# Led.net
KiCad netlist of a schematic drawn in Altium Designer
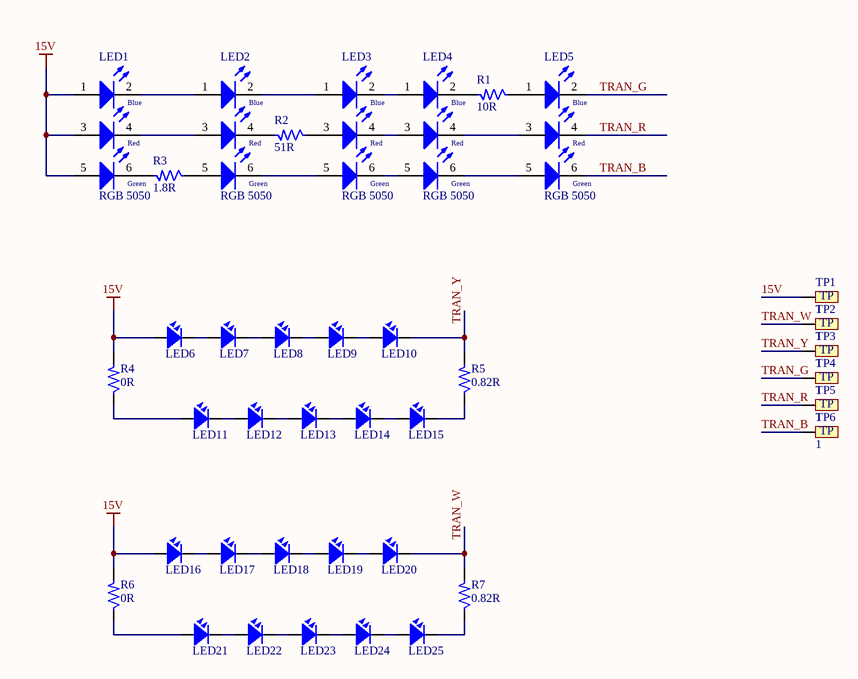
[diagram p0: Led.SchDoc]

(export (version "E")
  (design (tool "Eeschema 10.0.6"))
  (components
    (comp (ref "LED1")
      (value "RGB 5050")
      (footprint "HueNguyenLib:LED RGB 5050")
      (libsource (lib "HueNguyenLib") (part "LED RGB 5050 1.5W"))
    )
    (comp (ref "LED2")
      (value "RGB 5050")
      (footprint "HueNguyenLib:LED RGB 5050")
      (libsource (lib "HueNguyenLib") (part "LED RGB 5050 1.5W"))
    )
    (comp (ref "LED3")
      (value "RGB 5050")
      (footprint "HueNguyenLib:LED RGB 5050")
      (libsource (lib "HueNguyenLib") (part "LED RGB 5050 1.5W"))
    )
    (comp (ref "LED4")
      (value "RGB 5050")
      (footprint "HueNguyenLib:LED RGB 5050")
      (libsource (lib "HueNguyenLib") (part "LED RGB 5050 1.5W"))
    )
    (comp (ref "LED5")
      (value "RGB 5050")
      (footprint "HueNguyenLib:LED RGB 5050")
      (libsource (lib "HueNguyenLib") (part "LED RGB 5050 1.5W"))
    )
    (comp (ref "LED6")
      (value "3030")
      (footprint "HueNguyenLib:LED 3030")
      (libsource (lib "Thu Vien Chuan") (part "LED SMD"))
    )
    (comp (ref "LED7")
      (value "3030")
      (footprint "HueNguyenLib:LED 3030")
      (libsource (lib "Thu Vien Chuan") (part "LED SMD"))
    )
    (comp (ref "LED8")
      (value "3030")
      (footprint "HueNguyenLib:LED 3030")
      (libsource (lib "Thu Vien Chuan") (part "LED SMD"))
    )
    (comp (ref "LED9")
      (value "3030")
      (footprint "HueNguyenLib:LED 3030")
      (libsource (lib "Thu Vien Chuan") (part "LED SMD"))
    )
    (comp (ref "LED10")
      (value "3030")
      (footprint "HueNguyenLib:LED 3030")
      (libsource (lib "Thu Vien Chuan") (part "LED SMD"))
    )
    (comp (ref "LED11")
      (value "3030")
      (footprint "HueNguyenLib:LED 3030")
      (libsource (lib "Thu Vien Chuan") (part "LED SMD"))
    )
    (comp (ref "LED12")
      (value "3030")
      (footprint "HueNguyenLib:LED 3030")
      (libsource (lib "Thu Vien Chuan") (part "LED SMD"))
    )
    (comp (ref "LED13")
      (value "3030")
      (footprint "HueNguyenLib:LED 3030")
      (libsource (lib "Thu Vien Chuan") (part "LED SMD"))
    )
    (comp (ref "LED14")
      (value "3030")
      (footprint "HueNguyenLib:LED 3030")
      (libsource (lib "Thu Vien Chuan") (part "LED SMD"))
    )
    (comp (ref "LED15")
      (value "3030")
      (footprint "HueNguyenLib:LED 3030")
      (libsource (lib "Thu Vien Chuan") (part "LED SMD"))
    )
    (comp (ref "LED16")
      (value "3030")
      (footprint "HueNguyenLib:LED 3030")
      (libsource (lib "Thu Vien Chuan") (part "LED SMD"))
    )
    (comp (ref "LED17")
      (value "3030")
      (footprint "HueNguyenLib:LED 3030")
      (libsource (lib "Thu Vien Chuan") (part "LED SMD"))
    )
    (comp (ref "LED18")
      (value "3030")
      (footprint "HueNguyenLib:LED 3030")
      (libsource (lib "Thu Vien Chuan") (part "LED SMD"))
    )
    (comp (ref "LED19")
      (value "3030")
      (footprint "HueNguyenLib:LED 3030")
      (libsource (lib "Thu Vien Chuan") (part "LED SMD"))
    )
    (comp (ref "LED20")
      (value "3030")
      (footprint "HueNguyenLib:LED 3030")
      (libsource (lib "Thu Vien Chuan") (part "LED SMD"))
    )
    (comp (ref "LED21")
      (value "3030")
      (footprint "HueNguyenLib:LED 3030")
      (libsource (lib "Thu Vien Chuan") (part "LED SMD"))
    )
    (comp (ref "LED22")
      (value "3030")
      (footprint "HueNguyenLib:LED 3030")
      (libsource (lib "Thu Vien Chuan") (part "LED SMD"))
    )
    (comp (ref "LED23")
      (value "3030")
      (footprint "HueNguyenLib:LED 3030")
      (libsource (lib "Thu Vien Chuan") (part "LED SMD"))
    )
    (comp (ref "LED24")
      (value "3030")
      (footprint "HueNguyenLib:LED 3030")
      (libsource (lib "Thu Vien Chuan") (part "LED SMD"))
    )
    (comp (ref "LED25")
      (value "3030")
      (footprint "HueNguyenLib:LED 3030")
      (libsource (lib "Thu Vien Chuan") (part "LED SMD"))
    )
    (comp (ref "R1")
      (value "10R")
      (footprint "SM-RES-1206")
      (description "Resistor 1/4W")
      (libsource (lib "Thu Vien Chuan") (part "R"))
    )
    (comp (ref "R2")
      (value "51R")
      (footprint "SM-RES-1206")
      (description "Resistor 1/4W")
      (libsource (lib "Thu Vien Chuan") (part "R"))
    )
    (comp (ref "R3")
      (value "1.8R")
      (footprint "SM-RES-1206")
      (description "Resistor 1/4W")
      (libsource (lib "Thu Vien Chuan") (part "R"))
    )
    (comp (ref "R4")
      (value "0R")
      (footprint "SM-RES-1206")
      (description "Resistor 1/4W")
      (libsource (lib "Thu Vien Chuan") (part "R"))
    )
    (comp (ref "R5")
      (value "0.82R")
      (footprint "SM-RES-1206")
      (description "Resistor 1/4W")
      (libsource (lib "Thu Vien Chuan") (part "R"))
    )
    (comp (ref "R6")
      (value "0R")
      (footprint "SM-RES-1206")
      (description "Resistor 1/4W")
      (libsource (lib "Thu Vien Chuan") (part "R"))
    )
    (comp (ref "R7")
      (value "0.82R")
      (footprint "SM-RES-1206")
      (description "Resistor 1/4W")
      (libsource (lib "Thu Vien Chuan") (part "R"))
    )
    (comp (ref "TP1")
      (value "1")
      (footprint "TP")
      (description "CONNECT 1")
      (libsource (lib "Thu Vien Chuan") (part "TP"))
    )
    (comp (ref "TP2")
      (value "1")
      (footprint "TP")
      (description "CONNECT 1")
      (libsource (lib "Thu Vien Chuan") (part "TP"))
    )
    (comp (ref "TP3")
      (value "1")
      (footprint "TP")
      (description "CONNECT 1")
      (libsource (lib "Thu Vien Chuan") (part "TP"))
    )
    (comp (ref "TP4")
      (value "1")
      (footprint "TP")
      (description "CONNECT 1")
      (libsource (lib "Thu Vien Chuan") (part "TP"))
    )
    (comp (ref "TP5")
      (value "1")
      (footprint "TP")
      (description "CONNECT 1")
      (libsource (lib "Thu Vien Chuan") (part "TP"))
    )
    (comp (ref "TP6")
      (value "1")
      (footprint "TP")
      (description "CONNECT 1")
      (libsource (lib "Thu Vien Chuan") (part "TP"))
    )
  )
  (nets
    (net (code "1") (name "/TRAN_B") (class "Default")
      (node (ref "LED5") (pin "6") (pintype "passive"))
      (node (ref "TP6") (pin "TP1") (pinfunction "0_TP1") (pintype "passive"))
    )
    (net (code "2") (name "/TRAN_G") (class "Default")
      (node (ref "LED5") (pin "2") (pintype "passive"))
      (node (ref "TP4") (pin "TP1") (pinfunction "0_TP1") (pintype "passive"))
    )
    (net (code "3") (name "/TRAN_R") (class "Default")
      (node (ref "LED5") (pin "4") (pintype "passive"))
      (node (ref "TP5") (pin "TP1") (pinfunction "0_TP1") (pintype "passive"))
    )
    (net (code "4") (name "/TRAN_W") (class "Default")
      (node (ref "LED20") (pin "2") (pinfunction "2_2") (pintype "passive"))
      (node (ref "R7") (pin "2") (pinfunction "2_2") (pintype "passive"))
      (node (ref "TP2") (pin "TP1") (pinfunction "0_TP1") (pintype "passive"))
    )
    (net (code "5") (name "/TRAN_Y") (class "Default")
      (node (ref "LED10") (pin "2") (pinfunction "2_2") (pintype "passive"))
      (node (ref "R5") (pin "2") (pinfunction "2_2") (pintype "passive"))
      (node (ref "TP3") (pin "TP1") (pinfunction "0_TP1") (pintype "passive"))
    )
    (net (code "6") (name "15V") (class "Default")
      (node (ref "LED1") (pin "1") (pintype "passive"))
      (node (ref "LED1") (pin "3") (pintype "passive"))
      (node (ref "LED1") (pin "5") (pintype "passive"))
      (node (ref "LED16") (pin "1") (pinfunction "1_1") (pintype "passive"))
      (node (ref "LED6") (pin "1") (pinfunction "1_1") (pintype "passive"))
      (node (ref "R4") (pin "2") (pinfunction "2_2") (pintype "passive"))
      (node (ref "R6") (pin "2") (pinfunction "2_2") (pintype "passive"))
      (node (ref "TP1") (pin "TP1") (pinfunction "0_TP1") (pintype "passive"))
    )
    (net (code "7") (name "Net-(LED1-Pad2)") (class "Default")
      (node (ref "LED1") (pin "2") (pintype "passive"))
      (node (ref "LED2") (pin "1") (pintype "passive"))
    )
    (net (code "8") (name "Net-(LED1-Pad4)") (class "Default")
      (node (ref "LED1") (pin "4") (pintype "passive"))
      (node (ref "LED2") (pin "3") (pintype "passive"))
    )
    (net (code "9") (name "Net-(LED1-Pad6)") (class "Default")
      (node (ref "LED1") (pin "6") (pintype "passive"))
      (node (ref "R3") (pin "2") (pinfunction "2_2") (pintype "passive"))
    )
    (net (code "10") (name "Net-(LED2-Pad2)") (class "Default")
      (node (ref "LED2") (pin "2") (pintype "passive"))
      (node (ref "LED3") (pin "1") (pintype "passive"))
    )
    (net (code "11") (name "Net-(LED2-Pad4)") (class "Default")
      (node (ref "LED2") (pin "4") (pintype "passive"))
      (node (ref "R2") (pin "2") (pinfunction "2_2") (pintype "passive"))
    )
    (net (code "12") (name "Net-(LED2-Pad5)") (class "Default")
      (node (ref "LED2") (pin "5") (pintype "passive"))
      (node (ref "R3") (pin "1") (pinfunction "1_1") (pintype "passive"))
    )
    (net (code "13") (name "Net-(LED2-Pad6)") (class "Default")
      (node (ref "LED2") (pin "6") (pintype "passive"))
      (node (ref "LED3") (pin "5") (pintype "passive"))
    )
    (net (code "14") (name "Net-(LED3-Pad2)") (class "Default")
      (node (ref "LED3") (pin "2") (pintype "passive"))
      (node (ref "LED4") (pin "1") (pintype "passive"))
    )
    (net (code "15") (name "Net-(LED3-Pad3)") (class "Default")
      (node (ref "LED3") (pin "3") (pintype "passive"))
      (node (ref "R2") (pin "1") (pinfunction "1_1") (pintype "passive"))
    )
    (net (code "16") (name "Net-(LED3-Pad4)") (class "Default")
      (node (ref "LED3") (pin "4") (pintype "passive"))
      (node (ref "LED4") (pin "3") (pintype "passive"))
    )
    (net (code "17") (name "Net-(LED3-Pad6)") (class "Default")
      (node (ref "LED3") (pin "6") (pintype "passive"))
      (node (ref "LED4") (pin "5") (pintype "passive"))
    )
    (net (code "18") (name "Net-(LED4-Pad2)") (class "Default")
      (node (ref "LED4") (pin "2") (pintype "passive"))
      (node (ref "R1") (pin "2") (pinfunction "2_2") (pintype "passive"))
    )
    (net (code "19") (name "Net-(LED4-Pad4)") (class "Default")
      (node (ref "LED4") (pin "4") (pintype "passive"))
      (node (ref "LED5") (pin "3") (pintype "passive"))
    )
    (net (code "20") (name "Net-(LED4-Pad6)") (class "Default")
      (node (ref "LED4") (pin "6") (pintype "passive"))
      (node (ref "LED5") (pin "5") (pintype "passive"))
    )
    (net (code "21") (name "Net-(LED5-Pad1)") (class "Default")
      (node (ref "LED5") (pin "1") (pintype "passive"))
      (node (ref "R1") (pin "1") (pinfunction "1_1") (pintype "passive"))
    )
    (net (code "22") (name "Net-(LED6-Pad2)") (class "Default")
      (node (ref "LED6") (pin "2") (pinfunction "2_2") (pintype "passive"))
      (node (ref "LED7") (pin "1") (pinfunction "1_1") (pintype "passive"))
    )
    (net (code "23") (name "Net-(LED7-Pad2)") (class "Default")
      (node (ref "LED7") (pin "2") (pinfunction "2_2") (pintype "passive"))
      (node (ref "LED8") (pin "1") (pinfunction "1_1") (pintype "passive"))
    )
    (net (code "24") (name "Net-(LED8-Pad2)") (class "Default")
      (node (ref "LED8") (pin "2") (pinfunction "2_2") (pintype "passive"))
      (node (ref "LED9") (pin "1") (pinfunction "1_1") (pintype "passive"))
    )
    (net (code "25") (name "Net-(LED10-Pad1)") (class "Default")
      (node (ref "LED10") (pin "1") (pinfunction "1_1") (pintype "passive"))
      (node (ref "LED9") (pin "2") (pinfunction "2_2") (pintype "passive"))
    )
    (net (code "26") (name "Net-(LED11-Pad1)") (class "Default")
      (node (ref "LED11") (pin "1") (pinfunction "1_1") (pintype "passive"))
      (node (ref "R4") (pin "1") (pinfunction "1_1") (pintype "passive"))
    )
    (net (code "27") (name "Net-(LED11-Pad2)") (class "Default")
      (node (ref "LED11") (pin "2") (pinfunction "2_2") (pintype "passive"))
      (node (ref "LED12") (pin "1") (pinfunction "1_1") (pintype "passive"))
    )
    (net (code "28") (name "Net-(LED12-Pad2)") (class "Default")
      (node (ref "LED12") (pin "2") (pinfunction "2_2") (pintype "passive"))
      (node (ref "LED13") (pin "1") (pinfunction "1_1") (pintype "passive"))
    )
    (net (code "29") (name "Net-(LED13-Pad2)") (class "Default")
      (node (ref "LED13") (pin "2") (pinfunction "2_2") (pintype "passive"))
      (node (ref "LED14") (pin "1") (pinfunction "1_1") (pintype "passive"))
    )
    (net (code "30") (name "Net-(LED14-Pad2)") (class "Default")
      (node (ref "LED14") (pin "2") (pinfunction "2_2") (pintype "passive"))
      (node (ref "LED15") (pin "1") (pinfunction "1_1") (pintype "passive"))
    )
    (net (code "31") (name "Net-(LED15-Pad2)") (class "Default")
      (node (ref "LED15") (pin "2") (pinfunction "2_2") (pintype "passive"))
      (node (ref "R5") (pin "1") (pinfunction "1_1") (pintype "passive"))
    )
    (net (code "32") (name "Net-(LED16-Pad2)") (class "Default")
      (node (ref "LED16") (pin "2") (pinfunction "2_2") (pintype "passive"))
      (node (ref "LED17") (pin "1") (pinfunction "1_1") (pintype "passive"))
    )
    (net (code "33") (name "Net-(LED17-Pad2)") (class "Default")
      (node (ref "LED17") (pin "2") (pinfunction "2_2") (pintype "passive"))
      (node (ref "LED18") (pin "1") (pinfunction "1_1") (pintype "passive"))
    )
    (net (code "34") (name "Net-(LED18-Pad2)") (class "Default")
      (node (ref "LED18") (pin "2") (pinfunction "2_2") (pintype "passive"))
      (node (ref "LED19") (pin "1") (pinfunction "1_1") (pintype "passive"))
    )
    (net (code "35") (name "Net-(LED19-Pad2)") (class "Default")
      (node (ref "LED19") (pin "2") (pinfunction "2_2") (pintype "passive"))
      (node (ref "LED20") (pin "1") (pinfunction "1_1") (pintype "passive"))
    )
    (net (code "36") (name "Net-(LED21-Pad1)") (class "Default")
      (node (ref "LED21") (pin "1") (pinfunction "1_1") (pintype "passive"))
      (node (ref "R6") (pin "1") (pinfunction "1_1") (pintype "passive"))
    )
    (net (code "37") (name "Net-(LED21-Pad2)") (class "Default")
      (node (ref "LED21") (pin "2") (pinfunction "2_2") (pintype "passive"))
      (node (ref "LED22") (pin "1") (pinfunction "1_1") (pintype "passive"))
    )
    (net (code "38") (name "Net-(LED22-Pad2)") (class "Default")
      (node (ref "LED22") (pin "2") (pinfunction "2_2") (pintype "passive"))
      (node (ref "LED23") (pin "1") (pinfunction "1_1") (pintype "passive"))
    )
    (net (code "39") (name "Net-(LED23-Pad2)") (class "Default")
      (node (ref "LED23") (pin "2") (pinfunction "2_2") (pintype "passive"))
      (node (ref "LED24") (pin "1") (pinfunction "1_1") (pintype "passive"))
    )
    (net (code "40") (name "Net-(LED24-Pad2)") (class "Default")
      (node (ref "LED24") (pin "2") (pinfunction "2_2") (pintype "passive"))
      (node (ref "LED25") (pin "1") (pinfunction "1_1") (pintype "passive"))
    )
    (net (code "41") (name "Net-(LED25-Pad2)") (class "Default")
      (node (ref "LED25") (pin "2") (pinfunction "2_2") (pintype "passive"))
      (node (ref "R7") (pin "1") (pinfunction "1_1") (pintype "passive"))
    )
  )
)
